# SCH_cam_2026-07-08.net
KiCad netlist of a schematic drawn in EasyEDA
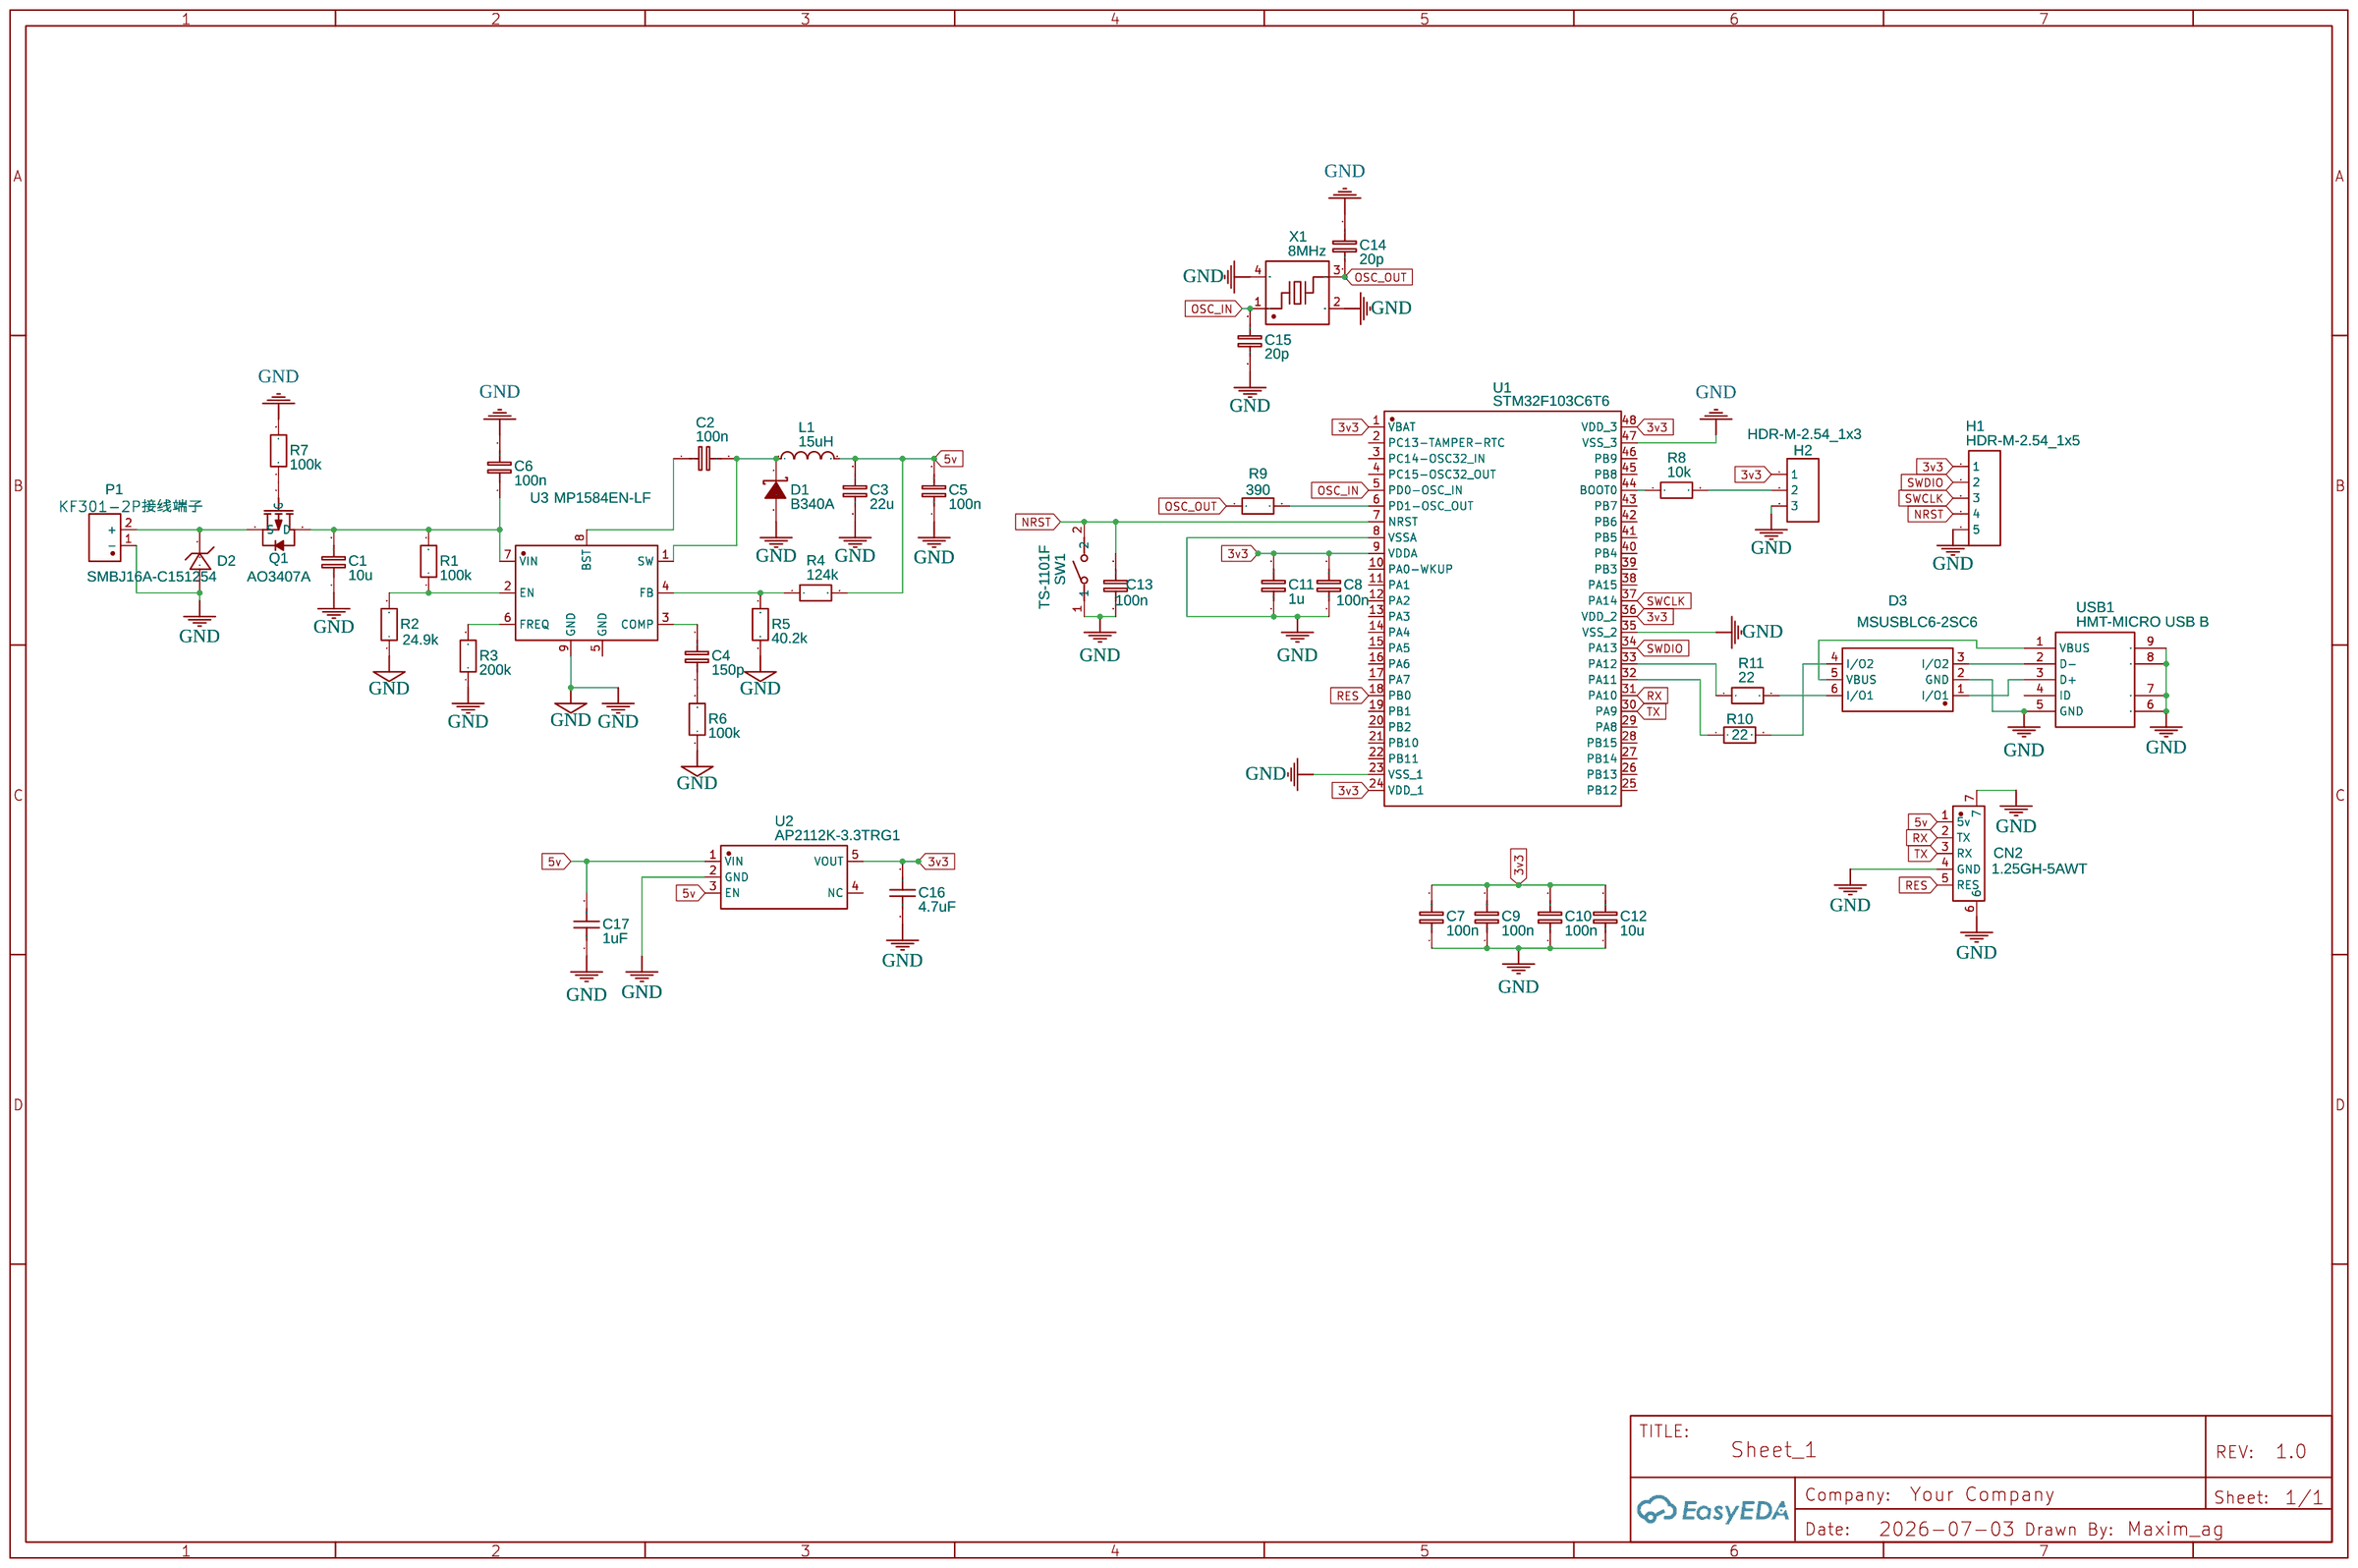
[diagram p0: schematic sheet]

(export (version "E")
  (design (tool "Eeschema 10.0.6"))
  (components
    (comp (ref "C1") (value "10u") (libsource (lib "") (part "C_1206_EU")))
    (comp (ref "C2") (value "100n") (libsource (lib "") (part "C_0805_EU_1")))
    (comp (ref "C3") (value "22u") (libsource (lib "") (part "C_1206_EU_1")))
    (comp (ref "C4") (value "150p") (libsource (lib "") (part "C_0805_EU_3")))
    (comp (ref "C5") (value "100n") (libsource (lib "") (part "C_0805_EU_4")))
    (comp (ref "C6") (value "100n") (libsource (lib "") (part "C_0805_EU_2")))
    (comp (ref "C7") (value "100n") (libsource (lib "") (part "C_0805_EU")))
    (comp (ref "C8") (value "100n") (libsource (lib "") (part "C_0805_EU")))
    (comp (ref "C9") (value "100n") (libsource (lib "") (part "C_0805_EU")))
    (comp (ref "C10") (value "100n") (libsource (lib "") (part "C_0805_EU")))
    (comp (ref "C11") (value "1u") (libsource (lib "") (part "C_0805_EU")))
    (comp (ref "C12") (value "10u") (libsource (lib "") (part "C_1206_EU_2")))
    (comp (ref "C13") (value "100n") (libsource (lib "") (part "C_0603_EU_1")))
    (comp (ref "C14") (value "20p") (libsource (lib "") (part "C_0603_EU")))
    (comp (ref "C15") (value "20p") (libsource (lib "") (part "C_0603_EU")))
    (comp (ref "C16")
      (value "4.7uF")
      (fields
        (field (name "Manufacturer Part") "0805X7R475K250NT")
        (field (name "Manufacturer") "AIDE(爱迪电容)")
      )
      (libsource (lib "") (part "0805X7R475K250NT"))
    )
    (comp (ref "C17")
      (value "1uF")
      (fields (field (name "Manufacturer") "AIDE(爱迪电容)"))
      (libsource (lib "") (part "0805X7R475K250NT"))
    )
    (comp (ref "CN2")
      (value "1.25GH-5AWT")
      (fields (field (name "Manufacturer") "FG(富港)"))
      (libsource (lib "") (part "1.25GH-5AWT"))
    )
    (comp (ref "D1")
      (value "B340A")
      (fields (field (name "Manufacturer") "MDD(辰达半导体)"))
      (libsource (lib "") (part "B340A"))
    )
    (comp (ref "D2")
      (value "SMBJ16A-C151254")
      (fields (field (name "Manufacturer Part") "SMBJ16A") (field (name "Manufacturer") "Littelfuse(美国力特)"))
      (libsource (lib "") (part "SMBJ16A-C151254"))
    )
    (comp (ref "D3")
      (value "MSUSBLC6-2SC6")
      (fields (field (name "Manufacturer") "MSKSEMI(美森科)"))
      (libsource (lib "") (part "MSUSBLC6-2SC6"))
    )
    (comp (ref "H1") (value "HDR-M-2.54_1x5") (libsource (lib "") (part "HDR-F-2.54_1x5")))
    (comp (ref "H2") (value "HDR-M-2.54_1x3") (libsource (lib "") (part "HDR-F-2.54_1x3")))
    (comp (ref "L1")
      (value "15uH")
      (fields (field (name "Manufacturer Part") "SLF10145T-100M2R5-H") (field (name "Manufacturer") "TDK"))
      (libsource (lib "") (part "SLF10145T-100M2R5-H"))
    )
    (comp (ref "P1") (value "KF301-2P接线端子") (libsource (lib "") (part "KF301-2P接线端子")))
    (comp (ref "Q1")
      (value "AO3407A")
      (fields (field (name "Manufacturer") "AOS"))
      (libsource (lib "") (part "AO3407A"))
    )
    (comp (ref "R1") (value "100k") (libsource (lib "") (part "R_0603_EU")))
    (comp (ref "R2") (value "24.9k") (libsource (lib "") (part "R_0603_EU")))
    (comp (ref "R3") (value "200k") (libsource (lib "") (part "R_0603_EU")))
    (comp (ref "R4") (value "124k") (libsource (lib "") (part "R_0805_EU_1")))
    (comp (ref "R5") (value "40.2k") (libsource (lib "") (part "R_0805_EU")))
    (comp (ref "R6") (value "100k") (libsource (lib "") (part "R_0805_EU")))
    (comp (ref "R7") (value "100k") (libsource (lib "") (part "R_0805_EU")))
    (comp (ref "R8") (value "10k") (libsource (lib "") (part "R_0805_EU_1")))
    (comp (ref "R9") (value "390") (libsource (lib "") (part "R_0603_EU_1")))
    (comp (ref "R10") (value "22") (libsource (lib "") (part "R_0603_EU_1")))
    (comp (ref "R11") (value "22") (libsource (lib "") (part "R_0603_EU_1")))
    (comp (ref "SW1") (value "TS-1101F") (libsource (lib "") (part "TS-1101F")))
    (comp (ref "U1") (value "STM32F103C6T6") (libsource (lib "") (part "STM32F103C6T6")))
    (comp (ref "U2")
      (value "AP2112K-3.3TRG1")
      (fields (field (name "Manufacturer") "DIODES(美台)"))
      (libsource (lib "") (part "AP2112K-3.3TRG1"))
    )
    (comp (ref "U3")
      (value "MP1584EN-LF")
      (fields (field (name "Manufacturer") "MPS(芯源)"))
      (libsource (lib "") (part "MP1584EN-LF"))
    )
    (comp (ref "USB1")
      (value "HMT-MICRO USB B")
      (fields (field (name "Manufacturer") "HMTCONN(华明通)"))
      (libsource (lib "") (part "HMT-MICRO USB B"))
    )
    (comp (ref "X1")
      (value "8MHz")
      (fields (field (name "Manufacturer Part") "X32258MSB4SI") (field (name "Manufacturer") "YXC(扬兴晶振)"))
      (libsource (lib "") (part "X32258MSB4SI"))
    )
  )
  (nets
    (net (code "1") (name "3v3") (class "Default")
      (node (ref "C10") (pin "2") (pinfunction "2_2") (pintype "unspecified"))
      (node (ref "C11") (pin "2") (pinfunction "2_2") (pintype "unspecified"))
      (node (ref "C12") (pin "2") (pinfunction "2_2") (pintype "unspecified"))
      (node (ref "C16") (pin "2") (pinfunction "2_2") (pintype "unspecified"))
      (node (ref "C7") (pin "2") (pinfunction "2_2") (pintype "unspecified"))
      (node (ref "C8") (pin "2") (pinfunction "2_2") (pintype "unspecified"))
      (node (ref "C9") (pin "2") (pinfunction "2_2") (pintype "unspecified"))
      (node (ref "H1") (pin "1") (pinfunction "1_1") (pintype "unspecified"))
      (node (ref "H2") (pin "1") (pinfunction "1_1") (pintype "input"))
      (node (ref "U1") (pin "1") (pinfunction "VBAT_1") (pintype "unspecified"))
      (node (ref "U1") (pin "24") (pinfunction "VDD_1_24") (pintype "unspecified"))
      (node (ref "U1") (pin "36") (pinfunction "VDD_2_36") (pintype "unspecified"))
      (node (ref "U1") (pin "48") (pinfunction "VDD_3_48") (pintype "unspecified"))
      (node (ref "U1") (pin "9") (pinfunction "VDDA_9") (pintype "unspecified"))
      (node (ref "U2") (pin "5") (pinfunction "VOUT_5") (pintype "unspecified"))
    )
    (net (code "2") (name "5v") (class "Default")
      (node (ref "C17") (pin "2") (pinfunction "2_2") (pintype "unspecified"))
      (node (ref "C3") (pin "2") (pinfunction "2_2") (pintype "unspecified"))
      (node (ref "C5") (pin "2") (pinfunction "2_2") (pintype "unspecified"))
      (node (ref "CN2") (pin "1") (pinfunction "5v_1") (pintype "unspecified"))
      (node (ref "L1") (pin "2") (pinfunction "2_2") (pintype "unspecified"))
      (node (ref "R4") (pin "2") (pinfunction "2_2") (pintype "unspecified"))
      (node (ref "U2") (pin "1") (pinfunction "VIN_1") (pintype "unspecified"))
      (node (ref "U2") (pin "3") (pinfunction "EN_3") (pintype "unspecified"))
    )
    (net (code "3") (name "GND") (class "Default")
      (node (ref "C1") (pin "1") (pinfunction "1_1") (pintype "unspecified"))
      (node (ref "C10") (pin "1") (pinfunction "1_1") (pintype "unspecified"))
      (node (ref "C11") (pin "1") (pinfunction "1_1") (pintype "unspecified"))
      (node (ref "C12") (pin "1") (pinfunction "1_1") (pintype "unspecified"))
      (node (ref "C13") (pin "1") (pinfunction "1_1") (pintype "unspecified"))
      (node (ref "C14") (pin "2") (pinfunction "2_2") (pintype "unspecified"))
      (node (ref "C15") (pin "1") (pinfunction "1_1") (pintype "unspecified"))
      (node (ref "C16") (pin "1") (pinfunction "1_1") (pintype "unspecified"))
      (node (ref "C17") (pin "1") (pinfunction "1_1") (pintype "unspecified"))
      (node (ref "C3") (pin "1") (pinfunction "1_1") (pintype "unspecified"))
      (node (ref "C5") (pin "1") (pinfunction "1_1") (pintype "unspecified"))
      (node (ref "C6") (pin "2") (pinfunction "2_2") (pintype "unspecified"))
      (node (ref "C7") (pin "1") (pinfunction "1_1") (pintype "unspecified"))
      (node (ref "C8") (pin "1") (pinfunction "1_1") (pintype "unspecified"))
      (node (ref "C9") (pin "1") (pinfunction "1_1") (pintype "unspecified"))
      (node (ref "CN2") (pin "4") (pinfunction "GND_4") (pintype "unspecified"))
      (node (ref "CN2") (pin "6") (pinfunction "6_6") (pintype "unspecified"))
      (node (ref "CN2") (pin "7") (pinfunction "7_7") (pintype "unspecified"))
      (node (ref "D1") (pin "2") (pinfunction "A_2") (pintype "unspecified"))
      (node (ref "D2") (pin "2") (pinfunction "A_2") (pintype "unspecified"))
      (node (ref "D3") (pin "2") (pinfunction "GND_2") (pintype "unspecified"))
      (node (ref "H1") (pin "5") (pinfunction "5_5") (pintype "unspecified"))
      (node (ref "H2") (pin "3") (pinfunction "3_3") (pintype "input"))
      (node (ref "P1") (pin "1") (pinfunction "-_1") (pintype "unspecified"))
      (node (ref "R2") (pin "1") (pinfunction "1_1") (pintype "unspecified"))
      (node (ref "R3") (pin "1") (pinfunction "1_1") (pintype "unspecified"))
      (node (ref "R5") (pin "1") (pinfunction "1_1") (pintype "unspecified"))
      (node (ref "R6") (pin "1") (pinfunction "1_1") (pintype "unspecified"))
      (node (ref "R7") (pin "2") (pinfunction "2_2") (pintype "unspecified"))
      (node (ref "SW1") (pin "1") (pinfunction "1_1") (pintype "unspecified"))
      (node (ref "U1") (pin "23") (pinfunction "VSS_1_23") (pintype "unspecified"))
      (node (ref "U1") (pin "35") (pinfunction "VSS_2_35") (pintype "unspecified"))
      (node (ref "U1") (pin "47") (pinfunction "VSS_3_47") (pintype "unspecified"))
      (node (ref "U1") (pin "8") (pinfunction "VSSA_8") (pintype "unspecified"))
      (node (ref "U2") (pin "2") (pinfunction "GND_2") (pintype "unspecified"))
      (node (ref "U3") (pin "9") (pinfunction "GND_9") (pintype "unspecified"))
      (node (ref "USB1") (pin "5") (pinfunction "GND_5") (pintype "unspecified"))
      (node (ref "USB1") (pin "6") (pinfunction "EH_6") (pintype "unspecified"))
      (node (ref "USB1") (pin "7") (pinfunction "EH_7") (pintype "unspecified"))
      (node (ref "USB1") (pin "8") (pinfunction "EH_8") (pintype "unspecified"))
      (node (ref "USB1") (pin "9") (pinfunction "EH_9") (pintype "unspecified"))
      (node (ref "X1") (pin "2") (pinfunction "GND_2") (pintype "input"))
      (node (ref "X1") (pin "4") (pinfunction "GND_4") (pintype "input"))
    )
    (net (code "4") (name "NRST") (class "Default")
      (node (ref "C13") (pin "2") (pinfunction "2_2") (pintype "unspecified"))
      (node (ref "H1") (pin "4") (pinfunction "4_4") (pintype "unspecified"))
      (node (ref "SW1") (pin "2") (pinfunction "2_2") (pintype "unspecified"))
      (node (ref "U1") (pin "7") (pinfunction "NRST_7") (pintype "unspecified"))
    )
    (net (code "5") (name "Net-(C4-Pad1)") (class "Default")
      (node (ref "C4") (pin "1") (pinfunction "1_1") (pintype "unspecified"))
      (node (ref "R6") (pin "2") (pinfunction "2_2") (pintype "unspecified"))
    )
    (net (code "6") (name "Net-(D1-K)") (class "Default")
      (node (ref "C2") (pin "2") (pinfunction "2_2") (pintype "unspecified"))
      (node (ref "D1") (pin "1") (pinfunction "K_1") (pintype "unspecified"))
      (node (ref "L1") (pin "1") (pinfunction "1_1") (pintype "unspecified"))
      (node (ref "U3") (pin "1") (pinfunction "SW_1") (pintype "unspecified"))
    )
    (net (code "7") (name "Net-(D2-C)") (class "Default")
      (node (ref "D2") (pin "1") (pinfunction "C_1") (pintype "unspecified"))
      (node (ref "P1") (pin "2") (pinfunction "+_2") (pintype "unspecified"))
      (node (ref "Q1") (pin "2") (pinfunction "S_2") (pintype "unspecified"))
    )
    (net (code "8") (name "Net-(D3-I{slash}O1-Pad6)") (class "Default")
      (node (ref "D3") (pin "6") (pinfunction "I/O1_6") (pintype "unspecified"))
      (node (ref "R11") (pin "2") (pinfunction "2_2") (pintype "unspecified"))
    )
    (net (code "9") (name "Net-(D3-I{slash}O2-Pad4)") (class "Default")
      (node (ref "D3") (pin "4") (pinfunction "I/O2_4") (pintype "unspecified"))
      (node (ref "R10") (pin "2") (pinfunction "2_2") (pintype "unspecified"))
    )
    (net (code "10") (name "Net-(D3-VBUS)") (class "Default")
      (node (ref "D3") (pin "5") (pinfunction "VBUS_5") (pintype "unspecified"))
      (node (ref "USB1") (pin "1") (pinfunction "VBUS_1") (pintype "unspecified"))
    )
    (net (code "11") (name "Net-(H2-Pad2)") (class "Default")
      (node (ref "H2") (pin "2") (pinfunction "2_2") (pintype "input"))
      (node (ref "R8") (pin "2") (pinfunction "2_2") (pintype "unspecified"))
    )
    (net (code "12") (name "Net-(Q1-D)") (class "Default")
      (node (ref "C1") (pin "2") (pinfunction "2_2") (pintype "unspecified"))
      (node (ref "C6") (pin "1") (pinfunction "1_1") (pintype "unspecified"))
      (node (ref "Q1") (pin "3") (pinfunction "D_3") (pintype "unspecified"))
      (node (ref "R1") (pin "2") (pinfunction "2_2") (pintype "unspecified"))
      (node (ref "U3") (pin "7") (pinfunction "VIN_7") (pintype "unspecified"))
    )
    (net (code "13") (name "Net-(Q1-G)") (class "Default")
      (node (ref "Q1") (pin "1") (pinfunction "G_1") (pintype "unspecified"))
      (node (ref "R7") (pin "1") (pinfunction "1_1") (pintype "unspecified"))
    )
    (net (code "14") (name "Net-(U1-BOOT0)") (class "Default")
      (node (ref "R8") (pin "1") (pinfunction "1_1") (pintype "unspecified"))
      (node (ref "U1") (pin "44") (pinfunction "BOOT0_44") (pintype "unspecified"))
    )
    (net (code "15") (name "Net-(U1-PA11)") (class "Default")
      (node (ref "R10") (pin "1") (pinfunction "1_1") (pintype "unspecified"))
      (node (ref "U1") (pin "32") (pinfunction "PA11_32") (pintype "unspecified"))
    )
    (net (code "16") (name "Net-(U1-PA12)") (class "Default")
      (node (ref "R11") (pin "1") (pinfunction "1_1") (pintype "unspecified"))
      (node (ref "U1") (pin "33") (pinfunction "PA12_33") (pintype "unspecified"))
    )
    (net (code "17") (name "Net-(U1-PD1-OSC_OUT)") (class "Default")
      (node (ref "R9") (pin "2") (pinfunction "2_2") (pintype "unspecified"))
      (node (ref "U1") (pin "6") (pinfunction "PD1-OSC_OUT_6") (pintype "unspecified"))
    )
    (net (code "18") (name "Net-(U3-BST)") (class "Default")
      (node (ref "C2") (pin "1") (pinfunction "1_1") (pintype "unspecified"))
      (node (ref "U3") (pin "8") (pinfunction "BST_8") (pintype "unspecified"))
    )
    (net (code "19") (name "Net-(U3-COMP)") (class "Default")
      (node (ref "C4") (pin "2") (pinfunction "2_2") (pintype "unspecified"))
      (node (ref "U3") (pin "3") (pinfunction "COMP_3") (pintype "unspecified"))
    )
    (net (code "20") (name "Net-(U3-EN)") (class "Default")
      (node (ref "R1") (pin "1") (pinfunction "1_1") (pintype "unspecified"))
      (node (ref "R2") (pin "2") (pinfunction "2_2") (pintype "unspecified"))
      (node (ref "U3") (pin "2") (pinfunction "EN_2") (pintype "unspecified"))
    )
    (net (code "21") (name "Net-(U3-FB)") (class "Default")
      (node (ref "R4") (pin "1") (pinfunction "1_1") (pintype "unspecified"))
      (node (ref "R5") (pin "2") (pinfunction "2_2") (pintype "unspecified"))
      (node (ref "U3") (pin "4") (pinfunction "FB_4") (pintype "unspecified"))
    )
    (net (code "22") (name "Net-(U3-FREQ)") (class "Default")
      (node (ref "R3") (pin "2") (pinfunction "2_2") (pintype "unspecified"))
      (node (ref "U3") (pin "6") (pinfunction "FREQ_6") (pintype "unspecified"))
    )
    (net (code "23") (name "Net-(USB1-D+)") (class "Default")
      (node (ref "D3") (pin "1") (pinfunction "I/O1_1") (pintype "unspecified"))
      (node (ref "USB1") (pin "3") (pinfunction "D+_3") (pintype "unspecified"))
    )
    (net (code "24") (name "Net-(USB1-D-)") (class "Default")
      (node (ref "D3") (pin "3") (pinfunction "I/O2_3") (pintype "unspecified"))
      (node (ref "USB1") (pin "2") (pinfunction "D-_2") (pintype "unspecified"))
    )
    (net (code "25") (name "OSC_IN") (class "Default")
      (node (ref "C15") (pin "2") (pinfunction "2_2") (pintype "unspecified"))
      (node (ref "U1") (pin "5") (pinfunction "PD0-OSC_IN_5") (pintype "unspecified"))
      (node (ref "X1") (pin "1") (pinfunction "1_1") (pintype "input"))
    )
    (net (code "26") (name "OSC_OUT") (class "Default")
      (node (ref "C14") (pin "1") (pinfunction "1_1") (pintype "unspecified"))
      (node (ref "R9") (pin "1") (pinfunction "1_1") (pintype "unspecified"))
      (node (ref "X1") (pin "3") (pinfunction "3_3") (pintype "input"))
    )
    (net (code "27") (name "RES") (class "Default")
      (node (ref "CN2") (pin "5") (pinfunction "RES_5") (pintype "unspecified"))
      (node (ref "U1") (pin "18") (pinfunction "PB0_18") (pintype "unspecified"))
    )
    (net (code "28") (name "RX") (class "Default")
      (node (ref "CN2") (pin "2") (pinfunction "TX_2") (pintype "unspecified"))
      (node (ref "U1") (pin "31") (pinfunction "PA10_31") (pintype "unspecified"))
    )
    (net (code "29") (name "SWCLK") (class "Default")
      (node (ref "H1") (pin "3") (pinfunction "3_3") (pintype "unspecified"))
      (node (ref "U1") (pin "37") (pinfunction "PA14_37") (pintype "unspecified"))
    )
    (net (code "30") (name "SWDIO") (class "Default")
      (node (ref "H1") (pin "2") (pinfunction "2_2") (pintype "unspecified"))
      (node (ref "U1") (pin "34") (pinfunction "PA13_34") (pintype "unspecified"))
    )
    (net (code "31") (name "TX") (class "Default")
      (node (ref "CN2") (pin "3") (pinfunction "RX_3") (pintype "unspecified"))
      (node (ref "U1") (pin "30") (pinfunction "PA9_30") (pintype "unspecified"))
    )
    (net (code "32") (name "unconnected-(U1-PA0-WKUP-Pad10)") (class "Default")
      (node (ref "U1") (pin "10") (pinfunction "PA0-WKUP_10") (pintype "unspecified"))
    )
    (net (code "33") (name "unconnected-(U1-PA1-Pad11)") (class "Default")
      (node (ref "U1") (pin "11") (pinfunction "PA1_11") (pintype "unspecified"))
    )
    (net (code "34") (name "unconnected-(U1-PA2-Pad12)") (class "Default")
      (node (ref "U1") (pin "12") (pinfunction "PA2_12") (pintype "unspecified"))
    )
    (net (code "35") (name "unconnected-(U1-PA3-Pad13)") (class "Default")
      (node (ref "U1") (pin "13") (pinfunction "PA3_13") (pintype "unspecified"))
    )
    (net (code "36") (name "unconnected-(U1-PA4-Pad14)") (class "Default")
      (node (ref "U1") (pin "14") (pinfunction "PA4_14") (pintype "unspecified"))
    )
    (net (code "37") (name "unconnected-(U1-PA5-Pad15)") (class "Default")
      (node (ref "U1") (pin "15") (pinfunction "PA5_15") (pintype "unspecified"))
    )
    (net (code "38") (name "unconnected-(U1-PA6-Pad16)") (class "Default")
      (node (ref "U1") (pin "16") (pinfunction "PA6_16") (pintype "unspecified"))
    )
    (net (code "39") (name "unconnected-(U1-PA7-Pad17)") (class "Default")
      (node (ref "U1") (pin "17") (pinfunction "PA7_17") (pintype "unspecified"))
    )
    (net (code "40") (name "unconnected-(U1-PA8-Pad29)") (class "Default")
      (node (ref "U1") (pin "29") (pinfunction "PA8_29") (pintype "unspecified"))
    )
    (net (code "41") (name "unconnected-(U1-PA15-Pad38)") (class "Default")
      (node (ref "U1") (pin "38") (pinfunction "PA15_38") (pintype "unspecified"))
    )
    (net (code "42") (name "unconnected-(U1-PB1-Pad19)") (class "Default")
      (node (ref "U1") (pin "19") (pinfunction "PB1_19") (pintype "unspecified"))
    )
    (net (code "43") (name "unconnected-(U1-PB2-Pad20)") (class "Default")
      (node (ref "U1") (pin "20") (pinfunction "PB2_20") (pintype "unspecified"))
    )
    (net (code "44") (name "unconnected-(U1-PB3-Pad39)") (class "Default")
      (node (ref "U1") (pin "39") (pinfunction "PB3_39") (pintype "unspecified"))
    )
    (net (code "45") (name "unconnected-(U1-PB4-Pad40)") (class "Default")
      (node (ref "U1") (pin "40") (pinfunction "PB4_40") (pintype "unspecified"))
    )
    (net (code "46") (name "unconnected-(U1-PB5-Pad41)") (class "Default")
      (node (ref "U1") (pin "41") (pinfunction "PB5_41") (pintype "unspecified"))
    )
    (net (code "47") (name "unconnected-(U1-PB6-Pad42)") (class "Default")
      (node (ref "U1") (pin "42") (pinfunction "PB6_42") (pintype "unspecified"))
    )
    (net (code "48") (name "unconnected-(U1-PB7-Pad43)") (class "Default")
      (node (ref "U1") (pin "43") (pinfunction "PB7_43") (pintype "unspecified"))
    )
    (net (code "49") (name "unconnected-(U1-PB8-Pad45)") (class "Default")
      (node (ref "U1") (pin "45") (pinfunction "PB8_45") (pintype "unspecified"))
    )
    (net (code "50") (name "unconnected-(U1-PB9-Pad46)") (class "Default")
      (node (ref "U1") (pin "46") (pinfunction "PB9_46") (pintype "unspecified"))
    )
    (net (code "51") (name "unconnected-(U1-PB10-Pad21)") (class "Default")
      (node (ref "U1") (pin "21") (pinfunction "PB10_21") (pintype "unspecified"))
    )
    (net (code "52") (name "unconnected-(U1-PB11-Pad22)") (class "Default")
      (node (ref "U1") (pin "22") (pinfunction "PB11_22") (pintype "unspecified"))
    )
    (net (code "53") (name "unconnected-(U1-PB12-Pad25)") (class "Default")
      (node (ref "U1") (pin "25") (pinfunction "PB12_25") (pintype "unspecified"))
    )
    (net (code "54") (name "unconnected-(U1-PB13-Pad26)") (class "Default")
      (node (ref "U1") (pin "26") (pinfunction "PB13_26") (pintype "unspecified"))
    )
    (net (code "55") (name "unconnected-(U1-PB14-Pad27)") (class "Default")
      (node (ref "U1") (pin "27") (pinfunction "PB14_27") (pintype "unspecified"))
    )
    (net (code "56") (name "unconnected-(U1-PB15-Pad28)") (class "Default")
      (node (ref "U1") (pin "28") (pinfunction "PB15_28") (pintype "unspecified"))
    )
    (net (code "57") (name "unconnected-(U1-PC13-TAMPER-RTC-Pad2)") (class "Default")
      (node (ref "U1") (pin "2") (pinfunction "PC13-TAMPER-RTC_2") (pintype "unspecified"))
    )
    (net (code "58") (name "unconnected-(U1-PC14-OSC32_IN-Pad3)") (class "Default")
      (node (ref "U1") (pin "3") (pinfunction "PC14-OSC32_IN_3") (pintype "unspecified"))
    )
    (net (code "59") (name "unconnected-(U1-PC15-OSC32_OUT-Pad4)") (class "Default")
      (node (ref "U1") (pin "4") (pinfunction "PC15-OSC32_OUT_4") (pintype "unspecified"))
    )
    (net (code "60") (name "unconnected-(U2-NC-Pad4)") (class "Default")
      (node (ref "U2") (pin "4") (pinfunction "NC_4") (pintype "unspecified"))
    )
    (net (code "61") (name "unconnected-(U3-GND-Pad5)") (class "Default")
      (node (ref "U3") (pin "5") (pinfunction "GND_5") (pintype "unspecified"))
    )
    (net (code "62") (name "unconnected-(USB1-ID-Pad4)") (class "Default")
      (node (ref "USB1") (pin "4") (pinfunction "ID_4") (pintype "unspecified"))
    )
  )
)
